# SheetMechanicals.net
KiCad netlist of a schematic drawn in Altium Designer
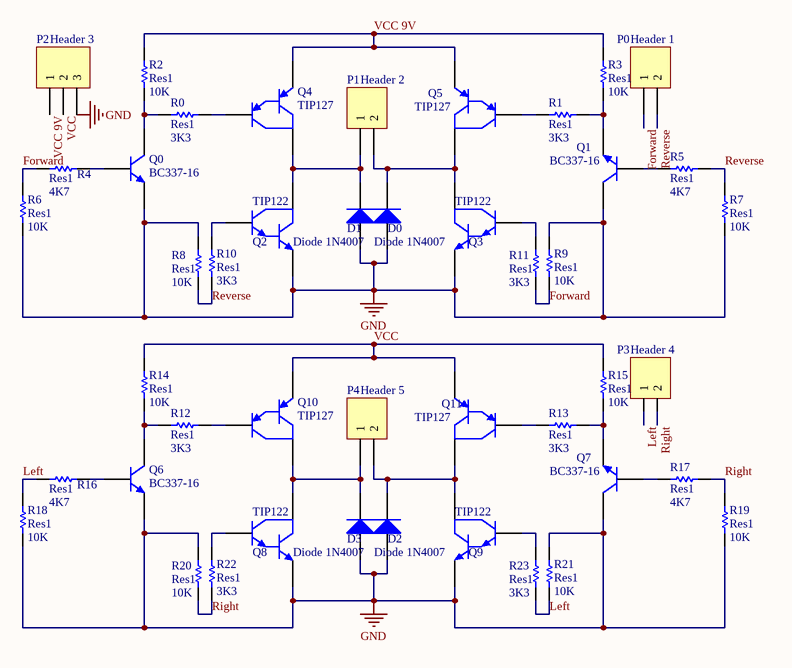
[diagram p0: SheetMechanicals.SchDoc]

(export (version "E")
  (design (tool "Eeschema 10.0.6"))
  (components
    (comp (ref "D0")
      (value "Diode 1N4007")
      (footprint "DO-41")
      (description "1 Amp General Purpose Rectifier")
      (fields (field (name "PUBLISHER") "Altium Limited"))
      (libsource (lib "Miscellaneous Devices") (part "Diode 1N4007"))
    )
    (comp (ref "D1")
      (value "Diode 1N4007")
      (footprint "DO-41")
      (description "1 Amp General Purpose Rectifier")
      (fields (field (name "PUBLISHER") "Altium Limited"))
      (libsource (lib "Miscellaneous Devices") (part "Diode 1N4007"))
    )
    (comp (ref "D2")
      (value "Diode 1N4007")
      (footprint "DO-41")
      (description "1 Amp General Purpose Rectifier")
      (fields (field (name "PUBLISHER") "Altium Limited"))
      (libsource (lib "Miscellaneous Devices") (part "Diode 1N4007"))
    )
    (comp (ref "D3")
      (value "Diode 1N4007")
      (footprint "DO-41")
      (description "1 Amp General Purpose Rectifier")
      (fields (field (name "PUBLISHER") "Altium Limited"))
      (libsource (lib "Miscellaneous Devices") (part "Diode 1N4007"))
    )
    (comp (ref "P0")
      (value "Header 1")
      (footprint "HDR1X2")
      (description "Header, 2-Pin")
      (fields (field (name "PUBLISHER") "Altium Limited"))
      (libsource (lib "Miscellaneous Connectors") (part "Header 2"))
    )
    (comp (ref "P1")
      (value "Header 2")
      (footprint "HDR1X2")
      (description "Header, 2-Pin")
      (fields (field (name "PUBLISHER") "Altium Limited"))
      (libsource (lib "Miscellaneous Connectors") (part "Header 2"))
    )
    (comp (ref "P2")
      (value "Header 3")
      (footprint "HDR1X3")
      (description "Header, 3-Pin")
      (fields (field (name "PUBLISHER") "Altium Limited"))
      (libsource (lib "Miscellaneous Connectors") (part "Header 3"))
    )
    (comp (ref "P3")
      (value "Header 4")
      (footprint "HDR1X2")
      (description "Header, 2-Pin")
      (fields (field (name "PUBLISHER") "Altium Limited"))
      (libsource (lib "Miscellaneous Connectors") (part "Header 2"))
    )
    (comp (ref "P4")
      (value "Header 5")
      (footprint "HDR1X2")
      (description "Header, 2-Pin")
      (fields (field (name "PUBLISHER") "Altium Limited"))
      (libsource (lib "Miscellaneous Connectors") (part "Header 2"))
    )
    (comp (ref "Q0")
      (value "BC337-16")
      (footprint "29-04")
      (description "Amplifier Transistor NPN Silicon")
      (fields (field (name "PUBLISHER") "Altium Limited"))
      (libsource (lib "Motorola Discrete BJT") (part "BC337-16"))
    )
    (comp (ref "Q1")
      (value "BC337-16")
      (footprint "29-04")
      (description "Amplifier Transistor NPN Silicon")
      (fields (field (name "PUBLISHER") "Altium Limited"))
      (libsource (lib "Motorola Discrete BJT") (part "BC337-16"))
    )
    (comp (ref "Q2")
      (value "TIP122")
      (footprint "221A-02")
      (description "Darlington Silicon Power NPN Transistor, 8 Amp, 100 Volts and 65 Watts")
      (fields (field (name "PUBLISHER") "Altium Limited"))
      (libsource (lib "Motorola Discrete BJT") (part "TIP122"))
    )
    (comp (ref "Q3")
      (value "TIP122")
      (footprint "221A-02")
      (description "Darlington Silicon Power NPN Transistor, 8 Amp, 100 Volts and 65 Watts")
      (fields (field (name "PUBLISHER") "Altium Limited"))
      (libsource (lib "Motorola Discrete BJT") (part "TIP122"))
    )
    (comp (ref "Q4")
      (value "TIP127")
      (footprint "221A-02")
      (description "Darlington Silicon Power PNP Transistor, 8 Amp, 100 Volts and 65 Watts")
      (fields (field (name "PUBLISHER") "Altium Limited"))
      (libsource (lib "Motorola Discrete BJT") (part "TIP127"))
    )
    (comp (ref "Q5")
      (value "TIP127")
      (footprint "221A-02")
      (description "Darlington Silicon Power PNP Transistor, 8 Amp, 100 Volts and 65 Watts")
      (fields (field (name "PUBLISHER") "Altium Limited"))
      (libsource (lib "Motorola Discrete BJT") (part "TIP127"))
    )
    (comp (ref "Q6")
      (value "BC337-16")
      (footprint "29-04")
      (description "Amplifier Transistor NPN Silicon")
      (fields (field (name "PUBLISHER") "Altium Limited"))
      (libsource (lib "Motorola Discrete BJT") (part "BC337-16"))
    )
    (comp (ref "Q7")
      (value "BC337-16")
      (footprint "29-04")
      (description "Amplifier Transistor NPN Silicon")
      (fields (field (name "PUBLISHER") "Altium Limited"))
      (libsource (lib "Motorola Discrete BJT") (part "BC337-16"))
    )
    (comp (ref "Q8")
      (value "TIP122")
      (footprint "221A-02")
      (description "Darlington Silicon Power NPN Transistor, 8 Amp, 100 Volts and 65 Watts")
      (fields (field (name "PUBLISHER") "Altium Limited"))
      (libsource (lib "Motorola Discrete BJT") (part "TIP122"))
    )
    (comp (ref "Q9")
      (value "TIP122")
      (footprint "221A-02")
      (description "Darlington Silicon Power NPN Transistor, 8 Amp, 100 Volts and 65 Watts")
      (fields (field (name "PUBLISHER") "Altium Limited"))
      (libsource (lib "Motorola Discrete BJT") (part "TIP122"))
    )
    (comp (ref "Q10")
      (value "TIP127")
      (footprint "221A-02")
      (description "Darlington Silicon Power PNP Transistor, 8 Amp, 100 Volts and 65 Watts")
      (fields (field (name "PUBLISHER") "Altium Limited"))
      (libsource (lib "Motorola Discrete BJT") (part "TIP127"))
    )
    (comp (ref "Q11")
      (value "TIP127")
      (footprint "221A-02")
      (description "Darlington Silicon Power PNP Transistor, 8 Amp, 100 Volts and 65 Watts")
      (fields (field (name "PUBLISHER") "Altium Limited"))
      (libsource (lib "Motorola Discrete BJT") (part "TIP127"))
    )
    (comp (ref "R0")
      (value "Res1")
      (footprint "AXIAL-0.3")
      (description "Resistor")
      (fields (field (name "ALTIUM_VALUE") "3K3") (field (name "PUBLISHER") "Altium Limited"))
      (libsource (lib "Miscellaneous Devices") (part "Res1"))
    )
    (comp (ref "R1")
      (value "Res1")
      (footprint "AXIAL-0.3")
      (description "Resistor")
      (fields (field (name "ALTIUM_VALUE") "3K3") (field (name "PUBLISHER") "Altium Limited"))
      (libsource (lib "Miscellaneous Devices") (part "Res1"))
    )
    (comp (ref "R2")
      (value "Res1")
      (footprint "AXIAL-0.3")
      (description "Resistor")
      (fields (field (name "ALTIUM_VALUE") "10K") (field (name "PUBLISHER") "Altium Limited"))
      (libsource (lib "Miscellaneous Devices") (part "Res1"))
    )
    (comp (ref "R3")
      (value "Res1")
      (footprint "AXIAL-0.3")
      (description "Resistor")
      (fields (field (name "ALTIUM_VALUE") "10K") (field (name "PUBLISHER") "Altium Limited"))
      (libsource (lib "Miscellaneous Devices") (part "Res1"))
    )
    (comp (ref "R4")
      (value "Res1")
      (footprint "AXIAL-0.3")
      (description "Resistor")
      (fields (field (name "ALTIUM_VALUE") "4K7") (field (name "PUBLISHER") "Altium Limited"))
      (libsource (lib "Miscellaneous Devices") (part "Res1"))
    )
    (comp (ref "R5")
      (value "Res1")
      (footprint "AXIAL-0.3")
      (description "Resistor")
      (fields (field (name "ALTIUM_VALUE") "4K7") (field (name "PUBLISHER") "Altium Limited"))
      (libsource (lib "Miscellaneous Devices") (part "Res1"))
    )
    (comp (ref "R6")
      (value "Res1")
      (footprint "AXIAL-0.3")
      (description "Resistor")
      (fields (field (name "ALTIUM_VALUE") "10K") (field (name "PUBLISHER") "Altium Limited"))
      (libsource (lib "Miscellaneous Devices") (part "Res1"))
    )
    (comp (ref "R7")
      (value "Res1")
      (footprint "AXIAL-0.3")
      (description "Resistor")
      (fields (field (name "ALTIUM_VALUE") "10K") (field (name "PUBLISHER") "Altium Limited"))
      (libsource (lib "Miscellaneous Devices") (part "Res1"))
    )
    (comp (ref "R8")
      (value "Res1")
      (footprint "AXIAL-0.3")
      (description "Resistor")
      (fields (field (name "ALTIUM_VALUE") "10K") (field (name "PUBLISHER") "Altium Limited"))
      (libsource (lib "Miscellaneous Devices") (part "Res1"))
    )
    (comp (ref "R9")
      (value "Res1")
      (footprint "AXIAL-0.3")
      (description "Resistor")
      (fields (field (name "ALTIUM_VALUE") "10K") (field (name "PUBLISHER") "Altium Limited"))
      (libsource (lib "Miscellaneous Devices") (part "Res1"))
    )
    (comp (ref "R10")
      (value "Res1")
      (footprint "AXIAL-0.3")
      (description "Resistor")
      (fields (field (name "ALTIUM_VALUE") "3K3") (field (name "PUBLISHER") "Altium Limited"))
      (libsource (lib "Miscellaneous Devices") (part "Res1"))
    )
    (comp (ref "R11")
      (value "Res1")
      (footprint "AXIAL-0.3")
      (description "Resistor")
      (fields (field (name "ALTIUM_VALUE") "3K3") (field (name "PUBLISHER") "Altium Limited"))
      (libsource (lib "Miscellaneous Devices") (part "Res1"))
    )
    (comp (ref "R12")
      (value "Res1")
      (footprint "AXIAL-0.3")
      (description "Resistor")
      (fields (field (name "ALTIUM_VALUE") "3K3") (field (name "PUBLISHER") "Altium Limited"))
      (libsource (lib "Miscellaneous Devices") (part "Res1"))
    )
    (comp (ref "R13")
      (value "Res1")
      (footprint "AXIAL-0.3")
      (description "Resistor")
      (fields (field (name "ALTIUM_VALUE") "3K3") (field (name "PUBLISHER") "Altium Limited"))
      (libsource (lib "Miscellaneous Devices") (part "Res1"))
    )
    (comp (ref "R14")
      (value "Res1")
      (footprint "AXIAL-0.3")
      (description "Resistor")
      (fields (field (name "ALTIUM_VALUE") "10K") (field (name "PUBLISHER") "Altium Limited"))
      (libsource (lib "Miscellaneous Devices") (part "Res1"))
    )
    (comp (ref "R15")
      (value "Res1")
      (footprint "AXIAL-0.3")
      (description "Resistor")
      (fields (field (name "ALTIUM_VALUE") "10K") (field (name "PUBLISHER") "Altium Limited"))
      (libsource (lib "Miscellaneous Devices") (part "Res1"))
    )
    (comp (ref "R16")
      (value "Res1")
      (footprint "AXIAL-0.3")
      (description "Resistor")
      (fields (field (name "ALTIUM_VALUE") "4K7") (field (name "PUBLISHER") "Altium Limited"))
      (libsource (lib "Miscellaneous Devices") (part "Res1"))
    )
    (comp (ref "R17")
      (value "Res1")
      (footprint "AXIAL-0.3")
      (description "Resistor")
      (fields (field (name "ALTIUM_VALUE") "4K7") (field (name "PUBLISHER") "Altium Limited"))
      (libsource (lib "Miscellaneous Devices") (part "Res1"))
    )
    (comp (ref "R18")
      (value "Res1")
      (footprint "AXIAL-0.3")
      (description "Resistor")
      (fields (field (name "ALTIUM_VALUE") "10K") (field (name "PUBLISHER") "Altium Limited"))
      (libsource (lib "Miscellaneous Devices") (part "Res1"))
    )
    (comp (ref "R19")
      (value "Res1")
      (footprint "AXIAL-0.3")
      (description "Resistor")
      (fields (field (name "ALTIUM_VALUE") "10K") (field (name "PUBLISHER") "Altium Limited"))
      (libsource (lib "Miscellaneous Devices") (part "Res1"))
    )
    (comp (ref "R20")
      (value "Res1")
      (footprint "AXIAL-0.3")
      (description "Resistor")
      (fields (field (name "ALTIUM_VALUE") "10K") (field (name "PUBLISHER") "Altium Limited"))
      (libsource (lib "Miscellaneous Devices") (part "Res1"))
    )
    (comp (ref "R21")
      (value "Res1")
      (footprint "AXIAL-0.3")
      (description "Resistor")
      (fields (field (name "ALTIUM_VALUE") "10K") (field (name "PUBLISHER") "Altium Limited"))
      (libsource (lib "Miscellaneous Devices") (part "Res1"))
    )
    (comp (ref "R22")
      (value "Res1")
      (footprint "AXIAL-0.3")
      (description "Resistor")
      (fields (field (name "ALTIUM_VALUE") "3K3") (field (name "PUBLISHER") "Altium Limited"))
      (libsource (lib "Miscellaneous Devices") (part "Res1"))
    )
    (comp (ref "R23")
      (value "Res1")
      (footprint "AXIAL-0.3")
      (description "Resistor")
      (fields (field (name "ALTIUM_VALUE") "3K3") (field (name "PUBLISHER") "Altium Limited"))
      (libsource (lib "Miscellaneous Devices") (part "Res1"))
    )
  )
  (nets
    (net (code "1") (name "/Forward") (class "Default")
      (node (ref "P0") (pin "1") (pinfunction "1_1") (pintype "passive"))
      (node (ref "R11") (pin "2") (pinfunction "2_2") (pintype "passive"))
      (node (ref "R4") (pin "1") (pinfunction "1_1") (pintype "passive"))
      (node (ref "R6") (pin "2") (pinfunction "2_2") (pintype "passive"))
      (node (ref "R9") (pin "2") (pinfunction "2_2") (pintype "passive"))
    )
    (net (code "2") (name "/Left") (class "Default")
      (node (ref "P3") (pin "1") (pinfunction "1_1") (pintype "passive"))
      (node (ref "R16") (pin "1") (pinfunction "1_1") (pintype "passive"))
      (node (ref "R18") (pin "2") (pinfunction "2_2") (pintype "passive"))
      (node (ref "R21") (pin "2") (pinfunction "2_2") (pintype "passive"))
      (node (ref "R23") (pin "2") (pinfunction "2_2") (pintype "passive"))
    )
    (net (code "3") (name "/Reverse") (class "Default")
      (node (ref "P0") (pin "2") (pinfunction "2_2") (pintype "passive"))
      (node (ref "R10") (pin "2") (pinfunction "2_2") (pintype "passive"))
      (node (ref "R5") (pin "2") (pinfunction "2_2") (pintype "passive"))
      (node (ref "R7") (pin "2") (pinfunction "2_2") (pintype "passive"))
      (node (ref "R8") (pin "2") (pinfunction "2_2") (pintype "passive"))
    )
    (net (code "4") (name "/Right") (class "Default")
      (node (ref "P3") (pin "2") (pinfunction "2_2") (pintype "passive"))
      (node (ref "R17") (pin "2") (pinfunction "2_2") (pintype "passive"))
      (node (ref "R19") (pin "2") (pinfunction "2_2") (pintype "passive"))
      (node (ref "R20") (pin "2") (pinfunction "2_2") (pintype "passive"))
      (node (ref "R22") (pin "2") (pinfunction "2_2") (pintype "passive"))
    )
    (net (code "5") (name "/VCC") (class "Default")
      (node (ref "P2") (pin "2") (pinfunction "2_2") (pintype "passive"))
      (node (ref "Q10") (pin "3") (pinfunction "E_3") (pintype "passive"))
      (node (ref "Q11") (pin "3") (pinfunction "E_3") (pintype "passive"))
      (node (ref "R14") (pin "1") (pinfunction "1_1") (pintype "passive"))
      (node (ref "R15") (pin "2") (pinfunction "2_2") (pintype "passive"))
    )
    (net (code "6") (name "/VCC 9V") (class "Default")
      (node (ref "P2") (pin "1") (pinfunction "1_1") (pintype "passive"))
      (node (ref "Q4") (pin "3") (pinfunction "E_3") (pintype "passive"))
      (node (ref "Q5") (pin "3") (pinfunction "E_3") (pintype "passive"))
      (node (ref "R2") (pin "1") (pinfunction "1_1") (pintype "passive"))
      (node (ref "R3") (pin "2") (pinfunction "2_2") (pintype "passive"))
    )
    (net (code "7") (name "GND") (class "Default")
      (node (ref "D0") (pin "1") (pinfunction "A_1") (pintype "passive"))
      (node (ref "D1") (pin "1") (pinfunction "A_1") (pintype "passive"))
      (node (ref "D2") (pin "1") (pinfunction "A_1") (pintype "passive"))
      (node (ref "D3") (pin "1") (pinfunction "A_1") (pintype "passive"))
      (node (ref "P2") (pin "3") (pinfunction "3_3") (pintype "passive"))
      (node (ref "Q0") (pin "3") (pinfunction "E_3") (pintype "passive"))
      (node (ref "Q1") (pin "1") (pinfunction "C_1") (pintype "passive"))
      (node (ref "Q2") (pin "3") (pinfunction "E_3") (pintype "passive"))
      (node (ref "Q3") (pin "3") (pinfunction "E_3") (pintype "passive"))
      (node (ref "Q6") (pin "3") (pinfunction "E_3") (pintype "passive"))
      (node (ref "Q7") (pin "1") (pinfunction "C_1") (pintype "passive"))
      (node (ref "Q8") (pin "3") (pinfunction "E_3") (pintype "passive"))
      (node (ref "Q9") (pin "3") (pinfunction "E_3") (pintype "passive"))
      (node (ref "R18") (pin "1") (pinfunction "1_1") (pintype "passive"))
      (node (ref "R19") (pin "1") (pinfunction "1_1") (pintype "passive"))
      (node (ref "R20") (pin "1") (pinfunction "1_1") (pintype "passive"))
      (node (ref "R21") (pin "1") (pinfunction "1_1") (pintype "passive"))
      (node (ref "R6") (pin "1") (pinfunction "1_1") (pintype "passive"))
      (node (ref "R7") (pin "1") (pinfunction "1_1") (pintype "passive"))
      (node (ref "R8") (pin "1") (pinfunction "1_1") (pintype "passive"))
      (node (ref "R9") (pin "1") (pinfunction "1_1") (pintype "passive"))
    )
    (net (code "8") (name "Net-(D0-K)") (class "Default")
      (node (ref "D0") (pin "2") (pinfunction "K_2") (pintype "passive"))
      (node (ref "P1") (pin "2") (pinfunction "2_2") (pintype "passive"))
      (node (ref "Q3") (pin "2") (pinfunction "C_2") (pintype "passive"))
      (node (ref "Q5") (pin "2") (pinfunction "C_2") (pintype "passive"))
    )
    (net (code "9") (name "Net-(D1-K)") (class "Default")
      (node (ref "D1") (pin "2") (pinfunction "K_2") (pintype "passive"))
      (node (ref "P1") (pin "1") (pinfunction "1_1") (pintype "passive"))
      (node (ref "Q2") (pin "2") (pinfunction "C_2") (pintype "passive"))
      (node (ref "Q4") (pin "2") (pinfunction "C_2") (pintype "passive"))
    )
    (net (code "10") (name "Net-(D2-K)") (class "Default")
      (node (ref "D2") (pin "2") (pinfunction "K_2") (pintype "passive"))
      (node (ref "P4") (pin "2") (pinfunction "2_2") (pintype "passive"))
      (node (ref "Q11") (pin "2") (pinfunction "C_2") (pintype "passive"))
      (node (ref "Q9") (pin "2") (pinfunction "C_2") (pintype "passive"))
    )
    (net (code "11") (name "Net-(D3-K)") (class "Default")
      (node (ref "D3") (pin "2") (pinfunction "K_2") (pintype "passive"))
      (node (ref "P4") (pin "1") (pinfunction "1_1") (pintype "passive"))
      (node (ref "Q10") (pin "2") (pinfunction "C_2") (pintype "passive"))
      (node (ref "Q8") (pin "2") (pinfunction "C_2") (pintype "passive"))
    )
    (net (code "12") (name "Net-(Q0-B)") (class "Default")
      (node (ref "Q0") (pin "2") (pinfunction "B_2") (pintype "passive"))
      (node (ref "R4") (pin "2") (pinfunction "2_2") (pintype "passive"))
    )
    (net (code "13") (name "Net-(Q0-C)") (class "Default")
      (node (ref "Q0") (pin "1") (pinfunction "C_1") (pintype "passive"))
      (node (ref "R0") (pin "1") (pinfunction "1_1") (pintype "passive"))
      (node (ref "R2") (pin "2") (pinfunction "2_2") (pintype "passive"))
    )
    (net (code "14") (name "Net-(Q1-B)") (class "Default")
      (node (ref "Q1") (pin "2") (pinfunction "B_2") (pintype "passive"))
      (node (ref "R5") (pin "1") (pinfunction "1_1") (pintype "passive"))
    )
    (net (code "15") (name "Net-(Q1-E)") (class "Default")
      (node (ref "Q1") (pin "3") (pinfunction "E_3") (pintype "passive"))
      (node (ref "R1") (pin "2") (pinfunction "2_2") (pintype "passive"))
      (node (ref "R3") (pin "1") (pinfunction "1_1") (pintype "passive"))
    )
    (net (code "16") (name "Net-(Q2-B)") (class "Default")
      (node (ref "Q2") (pin "1") (pinfunction "B_1") (pintype "passive"))
      (node (ref "R10") (pin "1") (pinfunction "1_1") (pintype "passive"))
    )
    (net (code "17") (name "Net-(Q3-B)") (class "Default")
      (node (ref "Q3") (pin "1") (pinfunction "B_1") (pintype "passive"))
      (node (ref "R11") (pin "1") (pinfunction "1_1") (pintype "passive"))
    )
    (net (code "18") (name "Net-(Q4-B)") (class "Default")
      (node (ref "Q4") (pin "1") (pinfunction "B_1") (pintype "passive"))
      (node (ref "R0") (pin "2") (pinfunction "2_2") (pintype "passive"))
    )
    (net (code "19") (name "Net-(Q5-B)") (class "Default")
      (node (ref "Q5") (pin "1") (pinfunction "B_1") (pintype "passive"))
      (node (ref "R1") (pin "1") (pinfunction "1_1") (pintype "passive"))
    )
    (net (code "20") (name "Net-(Q6-B)") (class "Default")
      (node (ref "Q6") (pin "2") (pinfunction "B_2") (pintype "passive"))
      (node (ref "R16") (pin "2") (pinfunction "2_2") (pintype "passive"))
    )
    (net (code "21") (name "Net-(Q6-C)") (class "Default")
      (node (ref "Q6") (pin "1") (pinfunction "C_1") (pintype "passive"))
      (node (ref "R12") (pin "1") (pinfunction "1_1") (pintype "passive"))
      (node (ref "R14") (pin "2") (pinfunction "2_2") (pintype "passive"))
    )
    (net (code "22") (name "Net-(Q7-B)") (class "Default")
      (node (ref "Q7") (pin "2") (pinfunction "B_2") (pintype "passive"))
      (node (ref "R17") (pin "1") (pinfunction "1_1") (pintype "passive"))
    )
    (net (code "23") (name "Net-(Q7-E)") (class "Default")
      (node (ref "Q7") (pin "3") (pinfunction "E_3") (pintype "passive"))
      (node (ref "R13") (pin "2") (pinfunction "2_2") (pintype "passive"))
      (node (ref "R15") (pin "1") (pinfunction "1_1") (pintype "passive"))
    )
    (net (code "24") (name "Net-(Q8-B)") (class "Default")
      (node (ref "Q8") (pin "1") (pinfunction "B_1") (pintype "passive"))
      (node (ref "R22") (pin "1") (pinfunction "1_1") (pintype "passive"))
    )
    (net (code "25") (name "Net-(Q9-B)") (class "Default")
      (node (ref "Q9") (pin "1") (pinfunction "B_1") (pintype "passive"))
      (node (ref "R23") (pin "1") (pinfunction "1_1") (pintype "passive"))
    )
    (net (code "26") (name "Net-(Q10-B)") (class "Default")
      (node (ref "Q10") (pin "1") (pinfunction "B_1") (pintype "passive"))
      (node (ref "R12") (pin "2") (pinfunction "2_2") (pintype "passive"))
    )
    (net (code "27") (name "Net-(Q11-B)") (class "Default")
      (node (ref "Q11") (pin "1") (pinfunction "B_1") (pintype "passive"))
      (node (ref "R13") (pin "1") (pinfunction "1_1") (pintype "passive"))
    )
  )
)
